# Qwiic-Bluetooth-HC1X.net
KiCad netlist of a schematic drawn in EAGLE
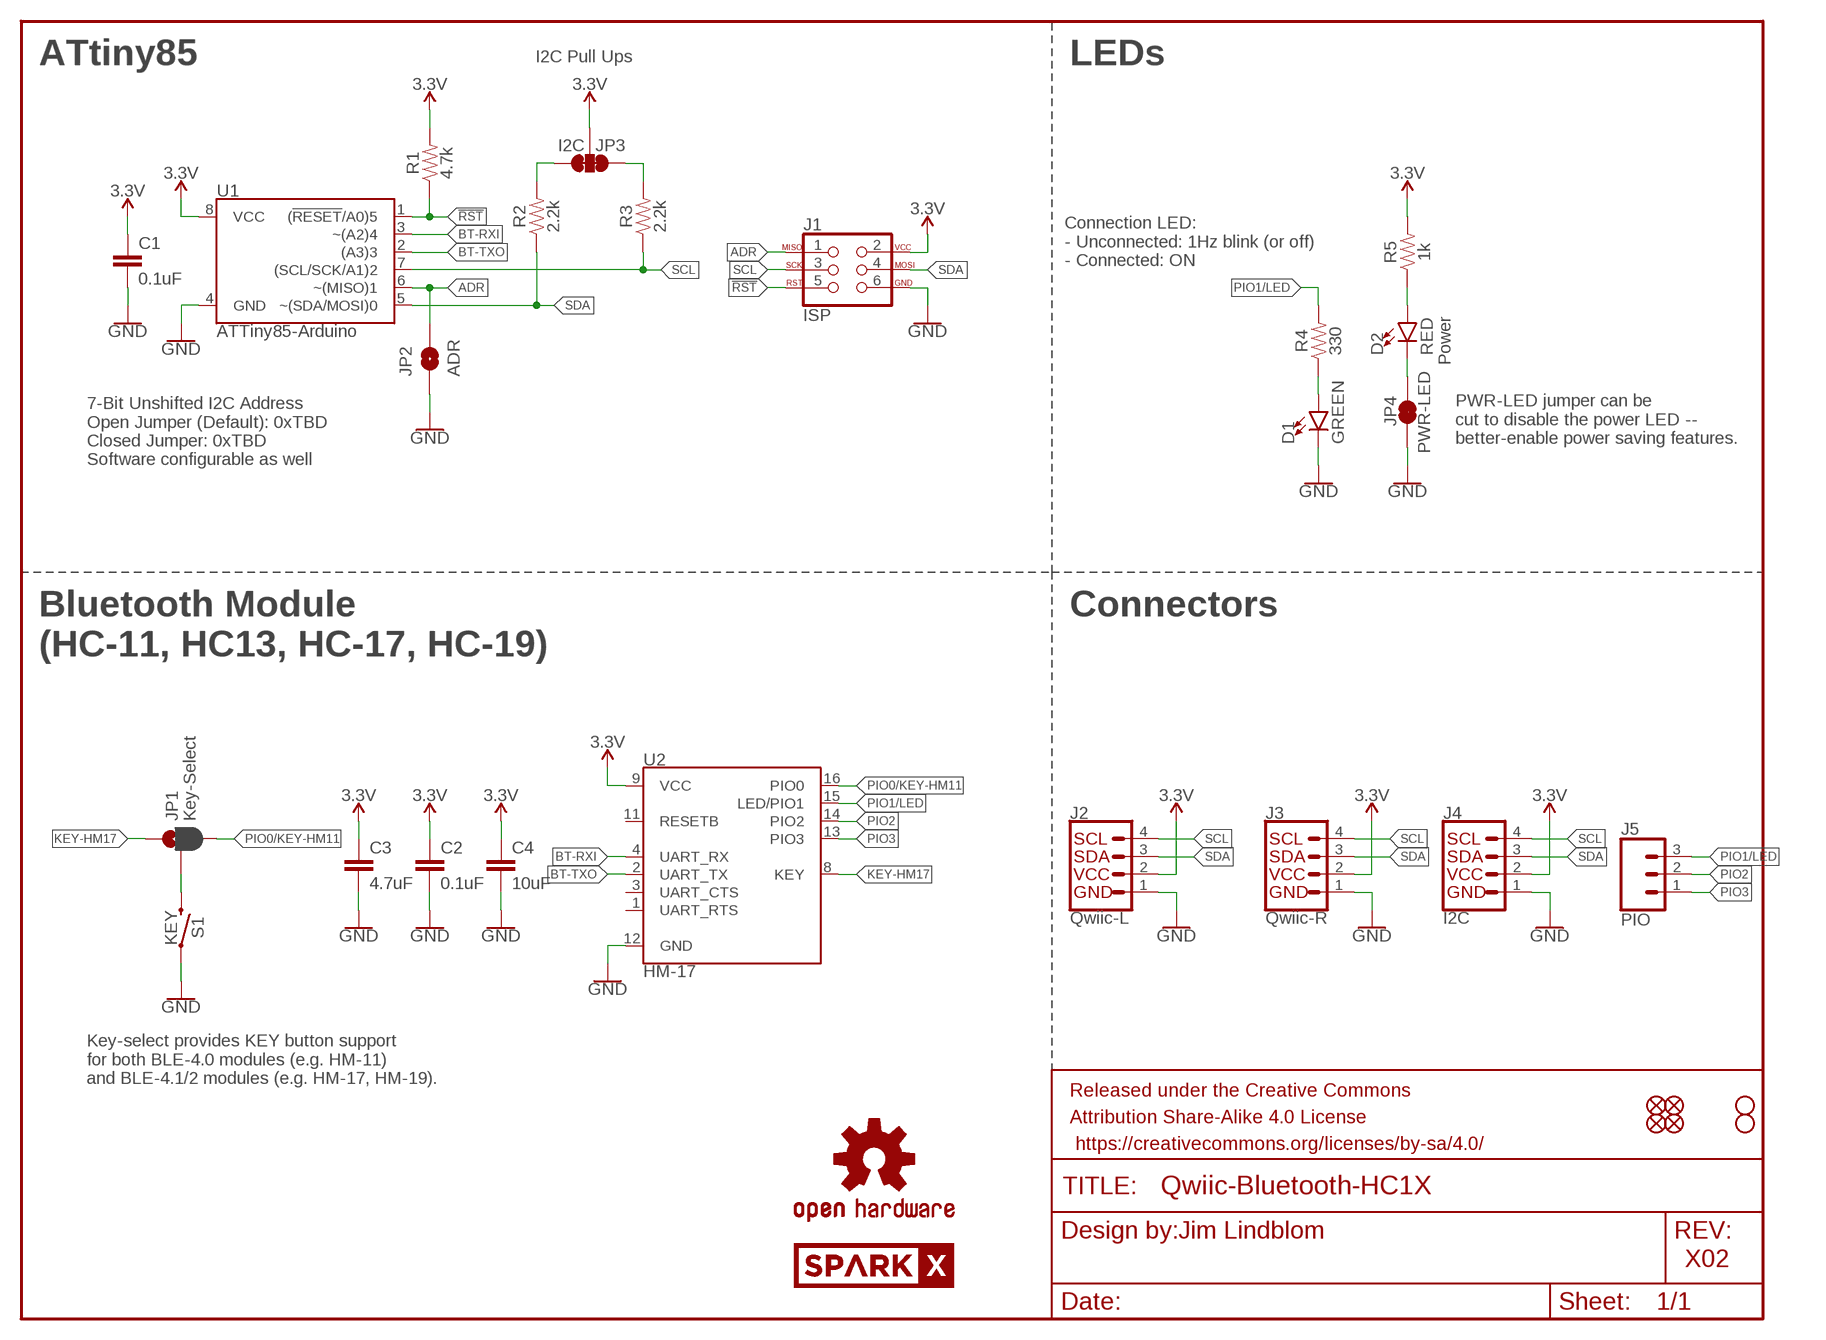
[diagram p0: schematic, sheet 1]

(export (version "E")
  (design (tool "Eeschema 10.0.6"))
  (components
    (comp (ref "C1")
      (value "0.1uF")
      (footprint "eagle-import:0603")
      (libsource (lib "eagle-import") (part "0.1UF-0603-25V-(+80/-20%)"))
    )
    (comp (ref "C2")
      (value "0.1uF")
      (footprint "eagle-import:0603")
      (libsource (lib "eagle-import") (part "0.1UF-0603-25V-(+80/-20%)"))
    )
    (comp (ref "C3")
      (value "4.7uF")
      (footprint "eagle-import:0603")
      (libsource (lib "eagle-import") (part "4.7UF-0603-6.3V-(10%)"))
    )
    (comp (ref "C4")
      (value "10uF")
      (footprint "eagle-import:0603")
      (libsource (lib "eagle-import") (part "10UF-0603-6.3V-20%"))
    )
    (comp (ref "D1")
      (value "GREEN")
      (footprint "eagle-import:LED-0603")
      (libsource (lib "eagle-import") (part "LED-GREEN0603"))
    )
    (comp (ref "D2")
      (value "RED")
      (footprint "eagle-import:LED-0603")
      (libsource (lib "eagle-import") (part "LED-RED0603"))
    )
    (comp (ref "FRAME1")
      (value "FRAME-LETTER")
      (footprint "eagle-import:CREATIVE_COMMONS")
      (libsource (lib "eagle-import") (part "FRAME-LETTER"))
    )
    (comp (ref "J1")
      (value "ISP")
      (footprint "eagle-import:2X3_TEST_POINTS")
      (libsource (lib "eagle-import") (part "AVR_SPI_PROG_3X2TESTPOINTS"))
    )
    (comp (ref "J2")
      (value "Qwiic-L")
      (footprint "eagle-import:1X04_1MM_RA")
      (libsource (lib "eagle-import") (part "QWIIC_CONNECTORJS-1MM"))
    )
    (comp (ref "J3")
      (value "Qwiic-R")
      (footprint "eagle-import:1X04_1MM_RA")
      (libsource (lib "eagle-import") (part "QWIIC_CONNECTORJS-1MM"))
    )
    (comp (ref "J4")
      (value "I2C")
      (footprint "eagle-import:1X04_NO_SILK")
      (libsource (lib "eagle-import") (part "I2C_STANDARD_NO_SILK"))
    )
    (comp (ref "J5")
      (value "PIO")
      (footprint "eagle-import:1X03_NO_SILK")
      (libsource (lib "eagle-import") (part "CONN_031X03_NO_SILK"))
    )
    (comp (ref "JP1")
      (value "Key-Select")
      (footprint "eagle-import:SMT-JUMPER_3_1-NC_PASTE_NO-SILK")
      (libsource (lib "eagle-import") (part "JUMPER-SMT_3_1-NC_PASTE_NO-SILK"))
    )
    (comp (ref "JP2")
      (value "ADR")
      (footprint "eagle-import:SMT-JUMPER_2_NO_NO-SILK")
      (libsource (lib "eagle-import") (part "JUMPER-SMT_2_NO_NO-SILK"))
    )
    (comp (ref "JP3")
      (value "I2C")
      (footprint "eagle-import:SMT-JUMPER_3_2-NC_TRACE_NO-SILK")
      (libsource (lib "eagle-import") (part "JUMPER-SMT_3_2-NC_TRACE_NO-SILK"))
    )
    (comp (ref "JP4")
      (value "PWR-LED")
      (footprint "eagle-import:SMT-JUMPER_2_NC_TRACE_NO-SILK")
      (libsource (lib "eagle-import") (part "JUMPER-SMT_2_NC_TRACE_NO-SILK"))
    )
    (comp (ref "JP5")
      (value "FIDUCIALUFIDUCIAL")
      (footprint "eagle-import:FIDUCIAL-MICRO")
      (libsource (lib "eagle-import") (part "FIDUCIALUFIDUCIAL"))
    )
    (comp (ref "JP6")
      (value "FIDUCIALUFIDUCIAL")
      (footprint "eagle-import:FIDUCIAL-MICRO")
      (libsource (lib "eagle-import") (part "FIDUCIALUFIDUCIAL"))
    )
    (comp (ref "JP7")
      (value "FIDUCIALUFIDUCIAL")
      (footprint "eagle-import:FIDUCIAL-MICRO")
      (libsource (lib "eagle-import") (part "FIDUCIALUFIDUCIAL"))
    )
    (comp (ref "JP8")
      (value "FIDUCIALUFIDUCIAL")
      (footprint "eagle-import:FIDUCIAL-MICRO")
      (libsource (lib "eagle-import") (part "FIDUCIALUFIDUCIAL"))
    )
    (comp (ref "JP11")
      (value "STAND-OFF")
      (footprint "eagle-import:STAND-OFF")
      (libsource (lib "eagle-import") (part "STAND-OFF"))
    )
    (comp (ref "JP12")
      (value "STAND-OFF")
      (footprint "eagle-import:STAND-OFF")
      (libsource (lib "eagle-import") (part "STAND-OFF"))
    )
    (comp (ref "LOGO1")
      (value "OSHW-LOGOMINI")
      (footprint "eagle-import:OSHW-LOGO-MINI")
      (libsource (lib "eagle-import") (part "OSHW-LOGOMINI"))
    )
    (comp (ref "LOGO2")
      (value "SPARKX-LOGO4")
      (footprint "eagle-import:SPARKX-MEDIUM")
      (libsource (lib "eagle-import") (part "SPARKX-LOGO4"))
    )
    (comp (ref "LOGO3")
      (value "SPARKX-LOGO4")
      (footprint "eagle-import:SPARKX-MEDIUM")
      (libsource (lib "eagle-import") (part "SPARKX-LOGO4"))
    )
    (comp (ref "R1")
      (value "4.7k")
      (footprint "eagle-import:0603")
      (libsource (lib "eagle-import") (part "4.7KOHM-0603-1/10W-1%"))
    )
    (comp (ref "R2")
      (value "2.2k")
      (footprint "eagle-import:0603")
      (libsource (lib "eagle-import") (part "2.2KOHM-0603-1/10W-1%"))
    )
    (comp (ref "R3")
      (value "2.2k")
      (footprint "eagle-import:0603")
      (libsource (lib "eagle-import") (part "2.2KOHM-0603-1/10W-1%"))
    )
    (comp (ref "R4")
      (value "330")
      (footprint "eagle-import:0603")
      (libsource (lib "eagle-import") (part "330OHM-0603-1/10W-1%"))
    )
    (comp (ref "R5")
      (value "1k")
      (footprint "eagle-import:0603")
      (libsource (lib "eagle-import") (part "1KOHM-0603-1/10W-1%"))
    )
    (comp (ref "S1")
      (value "KEY")
      (footprint "eagle-import:TACTILE_SWITCH_SMD_4.6X2.8MM")
      (libsource (lib "eagle-import") (part "MOMENTARY-SWITCH-SPST-SMD-4.6X2.8MM"))
    )
    (comp (ref "U1")
      (value "ATTiny85-Arduino")
      (footprint "eagle-import:SO08-EIAJ_MCU")
      (libsource (lib "eagle-import") (part "ATTINY85-ARDUINOTINY85-20-SMT"))
    )
    (comp (ref "U2")
      (value "HM-17")
      (footprint "eagle-import:HM-11")
      (libsource (lib "eagle-import") (part "HM-17"))
    )
  )
  (nets
    (net (code "1") (name "/~{RST}") (class "Default")
      (node (ref "J1") (pin "5") (pinfunction "5_5") (pintype "passive"))
      (node (ref "R1") (pin "1") (pinfunction "1_1") (pintype "passive"))
      (node (ref "U1") (pin "1") (pinfunction "(~{RESET}/A0)5_1") (pintype "bidirectional"))
    )
    (net (code "2") (name "3.3V") (class "Default")
      (node (ref "C1") (pin "1") (pinfunction "1_1") (pintype "passive"))
      (node (ref "C2") (pin "1") (pinfunction "1_1") (pintype "passive"))
      (node (ref "C3") (pin "1") (pinfunction "1_1") (pintype "passive"))
      (node (ref "C4") (pin "1") (pinfunction "1_1") (pintype "passive"))
      (node (ref "J1") (pin "2") (pinfunction "2_2") (pintype "passive"))
      (node (ref "J2") (pin "2") (pinfunction "2_2") (pintype "power_in"))
      (node (ref "J3") (pin "2") (pinfunction "2_2") (pintype "power_in"))
      (node (ref "J4") (pin "2") (pinfunction "VCC_2") (pintype "power_in"))
      (node (ref "JP3") (pin "2") (pinfunction "2_2") (pintype "passive"))
      (node (ref "R1") (pin "2") (pinfunction "2_2") (pintype "passive"))
      (node (ref "R5") (pin "2") (pinfunction "2_2") (pintype "passive"))
      (node (ref "U1") (pin "8") (pinfunction "VCC_8") (pintype "bidirectional"))
      (node (ref "U2") (pin "9") (pinfunction "VCC_9") (pintype "bidirectional"))
    )
    (net (code "3") (name "ADR") (class "Default")
      (node (ref "J1") (pin "1") (pinfunction "1_1") (pintype "passive"))
      (node (ref "JP2") (pin "2") (pinfunction "2_2") (pintype "passive"))
      (node (ref "U1") (pin "6") (pinfunction "~{(MISO})1_6") (pintype "bidirectional"))
    )
    (net (code "4") (name "BT-RXI") (class "Default")
      (node (ref "U1") (pin "3") (pinfunction "~{(A2})4_3") (pintype "bidirectional"))
      (node (ref "U2") (pin "4") (pinfunction "UART_RX_4") (pintype "bidirectional"))
    )
    (net (code "5") (name "BT-TXO") (class "Default")
      (node (ref "U1") (pin "2") (pinfunction "(A3)3_2") (pintype "bidirectional"))
      (node (ref "U2") (pin "2") (pinfunction "UART_TX_2") (pintype "bidirectional"))
    )
    (net (code "6") (name "GND") (class "Default")
      (node (ref "C1") (pin "2") (pinfunction "2_2") (pintype "passive"))
      (node (ref "C2") (pin "2") (pinfunction "2_2") (pintype "passive"))
      (node (ref "C3") (pin "2") (pinfunction "2_2") (pintype "passive"))
      (node (ref "C4") (pin "2") (pinfunction "2_2") (pintype "passive"))
      (node (ref "D1") (pin "C") (pinfunction "C_C") (pintype "passive"))
      (node (ref "J1") (pin "6") (pinfunction "6_6") (pintype "passive"))
      (node (ref "J2") (pin "1") (pinfunction "1_1") (pintype "power_in"))
      (node (ref "J3") (pin "1") (pinfunction "1_1") (pintype "power_in"))
      (node (ref "J4") (pin "1") (pinfunction "GND_1") (pintype "power_in"))
      (node (ref "JP2") (pin "1") (pinfunction "1_1") (pintype "passive"))
      (node (ref "JP4") (pin "1") (pinfunction "1_1") (pintype "passive"))
      (node (ref "S1") (pin "1") (pinfunction "1_1") (pintype "passive"))
      (node (ref "S1") (pin "2") (pinfunction "1_2") (pintype "passive"))
      (node (ref "U1") (pin "4") (pinfunction "GND_4") (pintype "bidirectional"))
      (node (ref "U2") (pin "12") (pinfunction "GND_12") (pintype "bidirectional"))
    )
    (net (code "7") (name "KEY-HM17") (class "Default")
      (node (ref "JP1") (pin "1") (pinfunction "1_1") (pintype "passive"))
      (node (ref "U2") (pin "8") (pinfunction "KEY_8") (pintype "bidirectional"))
    )
    (net (code "8") (name "Net-(D1-PadA)") (class "Default")
      (node (ref "D1") (pin "A") (pinfunction "A_A") (pintype "passive"))
      (node (ref "R4") (pin "1") (pinfunction "1_1") (pintype "passive"))
    )
    (net (code "9") (name "Net-(D2-PadA)") (class "Default")
      (node (ref "D2") (pin "A") (pinfunction "A_A") (pintype "passive"))
      (node (ref "R5") (pin "1") (pinfunction "1_1") (pintype "passive"))
    )
    (net (code "10") (name "Net-(D2-PadC)") (class "Default")
      (node (ref "D2") (pin "C") (pinfunction "C_C") (pintype "passive"))
      (node (ref "JP4") (pin "2") (pinfunction "2_2") (pintype "passive"))
    )
    (net (code "11") (name "Net-(JP1-Pad2)") (class "Default")
      (node (ref "JP1") (pin "2") (pinfunction "2_2") (pintype "passive"))
      (node (ref "S1") (pin "3") (pinfunction "2_3") (pintype "passive"))
      (node (ref "S1") (pin "4") (pinfunction "2_4") (pintype "passive"))
    )
    (net (code "12") (name "Net-(JP3-Pad1)") (class "Default")
      (node (ref "JP3") (pin "1") (pinfunction "1_1") (pintype "passive"))
      (node (ref "R3") (pin "2") (pinfunction "2_2") (pintype "passive"))
    )
    (net (code "13") (name "Net-(JP3-Pad3)") (class "Default")
      (node (ref "JP3") (pin "3") (pinfunction "3_3") (pintype "passive"))
      (node (ref "R2") (pin "2") (pinfunction "2_2") (pintype "passive"))
    )
    (net (code "14") (name "PIO0{slash}KEY-HM11") (class "Default")
      (node (ref "JP1") (pin "3") (pinfunction "3_3") (pintype "passive"))
      (node (ref "U2") (pin "16") (pinfunction "PIO0_16") (pintype "bidirectional"))
    )
    (net (code "15") (name "PIO1{slash}LED") (class "Default")
      (node (ref "J5") (pin "3") (pinfunction "3_3") (pintype "passive"))
      (node (ref "R4") (pin "2") (pinfunction "2_2") (pintype "passive"))
      (node (ref "U2") (pin "15") (pinfunction "LED/PIO1_15") (pintype "bidirectional"))
    )
    (net (code "16") (name "PIO2") (class "Default")
      (node (ref "J5") (pin "2") (pinfunction "2_2") (pintype "passive"))
      (node (ref "U2") (pin "14") (pinfunction "PIO2_14") (pintype "bidirectional"))
    )
    (net (code "17") (name "PIO3") (class "Default")
      (node (ref "J5") (pin "1") (pinfunction "1_1") (pintype "passive"))
      (node (ref "U2") (pin "13") (pinfunction "PIO3_13") (pintype "bidirectional"))
    )
    (net (code "18") (name "SCL") (class "Default")
      (node (ref "J1") (pin "3") (pinfunction "3_3") (pintype "passive"))
      (node (ref "J2") (pin "4") (pinfunction "4_4") (pintype "passive"))
      (node (ref "J3") (pin "4") (pinfunction "4_4") (pintype "passive"))
      (node (ref "J4") (pin "4") (pinfunction "SCL_4") (pintype "passive"))
      (node (ref "R3") (pin "1") (pinfunction "1_1") (pintype "passive"))
      (node (ref "U1") (pin "7") (pinfunction "(SCL/SCK/A1)2_7") (pintype "bidirectional"))
    )
    (net (code "19") (name "SDA") (class "Default")
      (node (ref "J1") (pin "4") (pinfunction "4_4") (pintype "passive"))
      (node (ref "J2") (pin "3") (pinfunction "3_3") (pintype "passive"))
      (node (ref "J3") (pin "3") (pinfunction "3_3") (pintype "passive"))
      (node (ref "J4") (pin "3") (pinfunction "SDA_3") (pintype "passive"))
      (node (ref "R2") (pin "1") (pinfunction "1_1") (pintype "passive"))
      (node (ref "U1") (pin "5") (pinfunction "~{(SDA/MOSI})0_5") (pintype "bidirectional"))
    )
    (net (code "20") (name "unconnected-(U2-RESETB-Pad11)") (class "Default")
      (node (ref "U2") (pin "11") (pinfunction "RESETB_11") (pintype "bidirectional"))
    )
    (net (code "21") (name "unconnected-(U2-UART_CTS-Pad3)") (class "Default")
      (node (ref "U2") (pin "3") (pinfunction "UART_CTS_3") (pintype "bidirectional"))
    )
    (net (code "22") (name "unconnected-(U2-UART_RTS-Pad1)") (class "Default")
      (node (ref "U2") (pin "1") (pinfunction "UART_RTS_1") (pintype "bidirectional"))
    )
  )
)
